# SparkFun-74HC4051-8-Channel-Mux-Breakout.net
KiCad netlist of a schematic drawn in EAGLE
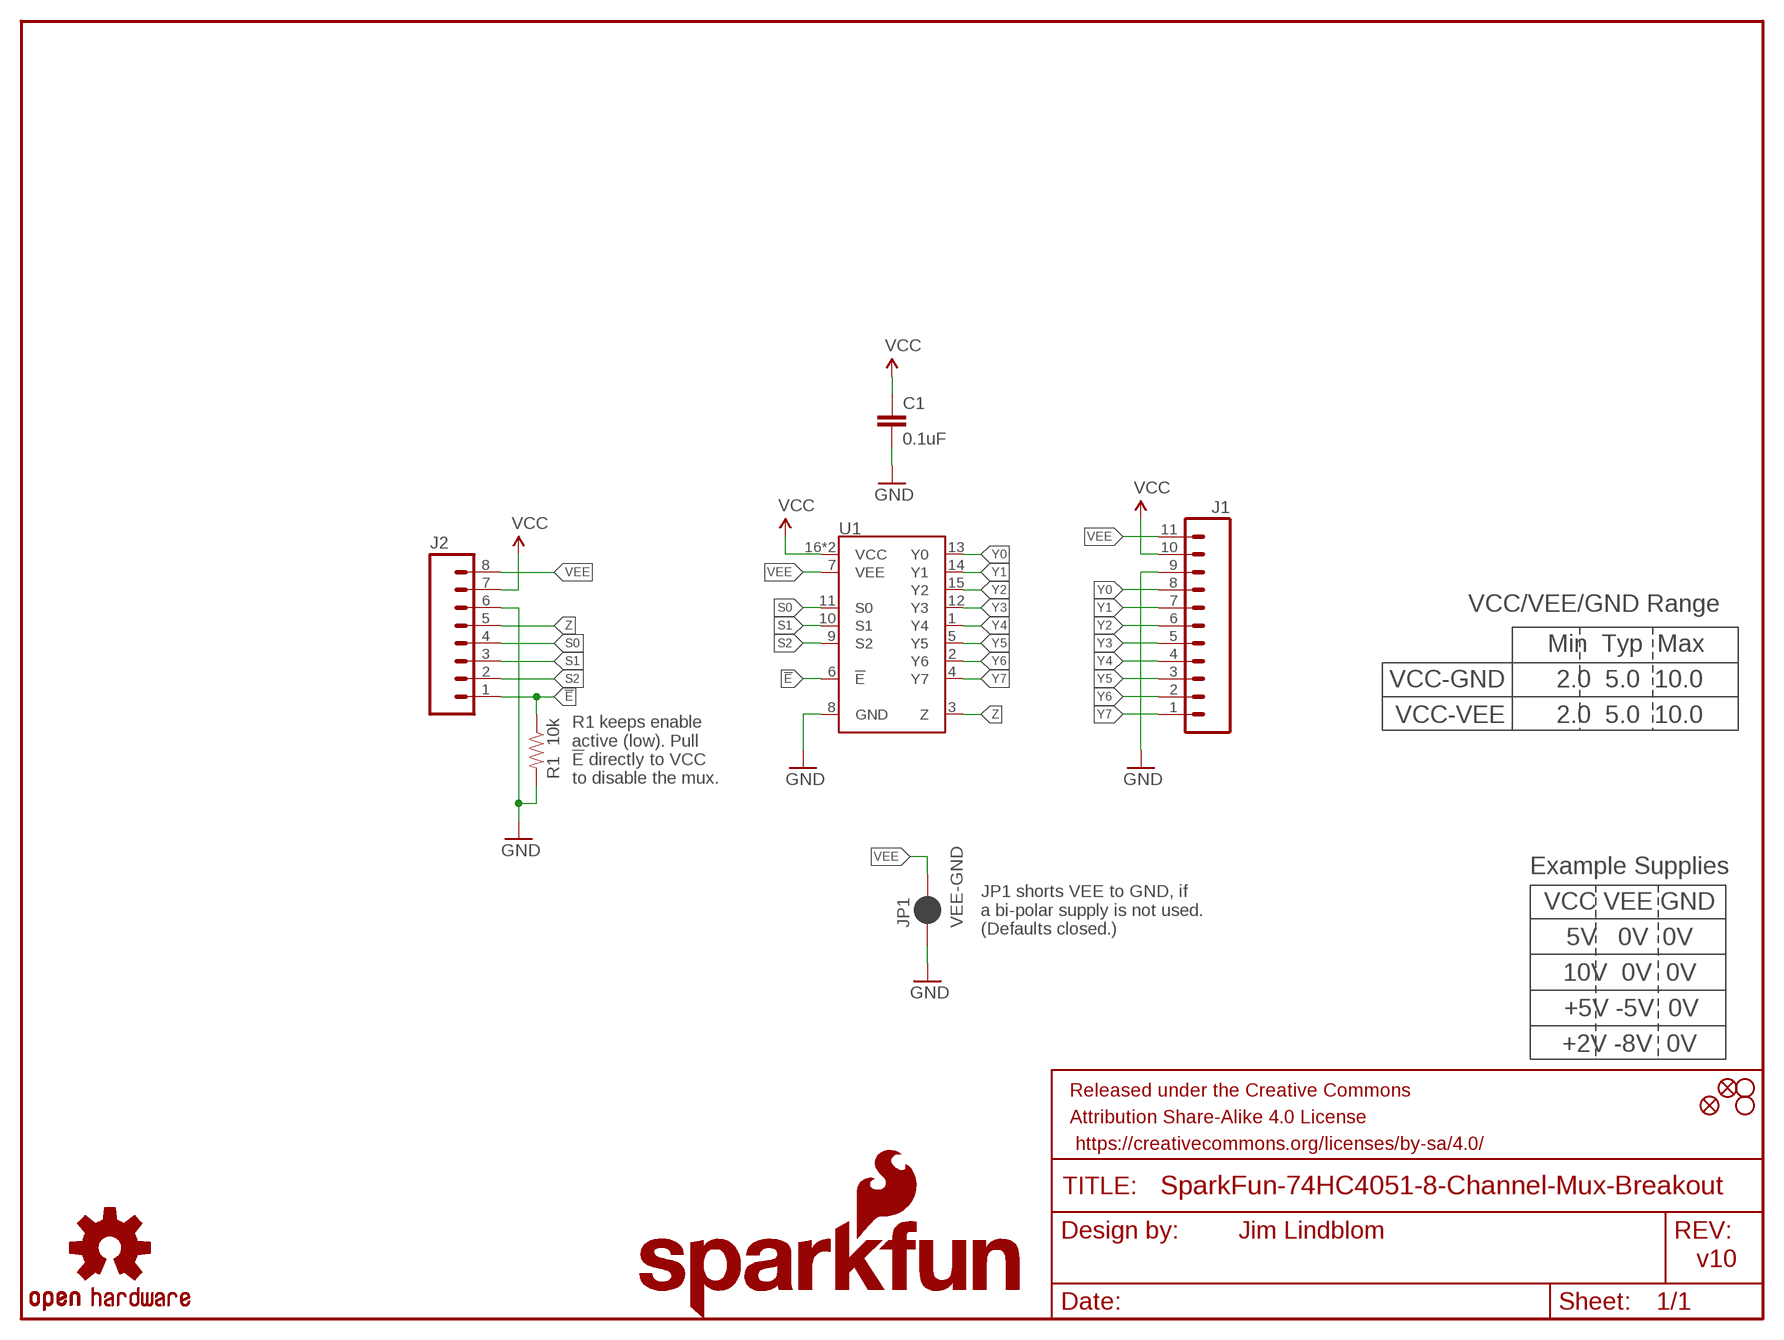
[diagram p0: schematic, sheet 1]

(export (version "E")
  (design (tool "Eeschema 10.0.6"))
  (components
    (comp (ref "C1")
      (value "0.1uF")
      (footprint "eagle-import:0603")
      (libsource (lib "eagle-import") (part "0.1UF-0603-25V-(+80/-20%)"))
    )
    (comp (ref "FD1")
      (value "FIDUCIAL1X2")
      (footprint "eagle-import:FIDUCIAL-1X2")
      (libsource (lib "eagle-import") (part "FIDUCIAL1X2"))
    )
    (comp (ref "FD2")
      (value "FIDUCIAL1X2")
      (footprint "eagle-import:FIDUCIAL-1X2")
      (libsource (lib "eagle-import") (part "FIDUCIAL1X2"))
    )
    (comp (ref "FRAME1")
      (value "FRAME-LETTER")
      (footprint "eagle-import:CREATIVE_COMMONS")
      (libsource (lib "eagle-import") (part "FRAME-LETTER"))
    )
    (comp (ref "H1")
      (value "STAND-OFF")
      (footprint "eagle-import:STAND-OFF")
      (libsource (lib "eagle-import") (part "STAND-OFF"))
    )
    (comp (ref "H2")
      (value "STAND-OFF")
      (footprint "eagle-import:STAND-OFF")
      (libsource (lib "eagle-import") (part "STAND-OFF"))
    )
    (comp (ref "J1")
      (value "M11PTH")
      (footprint "eagle-import:1X11")
      (libsource (lib "eagle-import") (part "M11PTH"))
    )
    (comp (ref "J2")
      (value "M08")
      (footprint "eagle-import:1X08_ROUND")
      (libsource (lib "eagle-import") (part "M08"))
    )
    (comp (ref "JP1")
      (value "VEE-GND")
      (footprint "eagle-import:PAD-JUMPER-2-NC_BY_PASTE_NO_SILK")
      (libsource (lib "eagle-import") (part "JUMPER-PAD-2-NC_BY_PASTENO-SILK"))
    )
    (comp (ref "LOGO1")
      (value "SFE_LOGO_FLAME.1_INCH")
      (footprint "eagle-import:SFE_LOGO_FLAME_.1")
      (libsource (lib "eagle-import") (part "SFE_LOGO_FLAME.1_INCH"))
    )
    (comp (ref "LOGO2")
      (value "OSHW-LOGOMINI")
      (footprint "eagle-import:OSHW-LOGO-MINI")
      (libsource (lib "eagle-import") (part "OSHW-LOGOMINI"))
    )
    (comp (ref "LOGO3")
      (value "SFE_LOGO_NAME.1_INCH")
      (footprint "eagle-import:SFE_LOGO_NAME_.1")
      (libsource (lib "eagle-import") (part "SFE_LOGO_NAME.1_INCH"))
    )
    (comp (ref "R1")
      (value "10k")
      (footprint "eagle-import:0603")
      (libsource (lib "eagle-import") (part "10KOHM-0603-1/10W-1%"))
    )
    (comp (ref "U1")
      (value "74HC4051BQ")
      (footprint "eagle-import:DHVQFN-16-2.5X3.5MM")
      (libsource (lib "eagle-import") (part "744051BQHC"))
    )
  )
  (nets
    (net (code "1") (name "/~{E}") (class "Default")
      (node (ref "J2") (pin "1") (pinfunction "1_1") (pintype "passive"))
      (node (ref "R1") (pin "1") (pinfunction "1_1") (pintype "passive"))
      (node (ref "U1") (pin "6") (pinfunction "~{E}_6") (pintype "bidirectional"))
    )
    (net (code "2") (name "GND") (class "Default")
      (node (ref "C1") (pin "2") (pinfunction "2_2") (pintype "passive"))
      (node (ref "J1") (pin "9") (pinfunction "9_9") (pintype "passive"))
      (node (ref "J2") (pin "6") (pinfunction "6_6") (pintype "passive"))
      (node (ref "JP1") (pin "1") (pinfunction "1_1") (pintype "passive"))
      (node (ref "R1") (pin "2") (pinfunction "2_2") (pintype "passive"))
      (node (ref "U1") (pin "8") (pinfunction "GND_8") (pintype "bidirectional"))
    )
    (net (code "3") (name "S0") (class "Default")
      (node (ref "J2") (pin "4") (pinfunction "4_4") (pintype "passive"))
      (node (ref "U1") (pin "11") (pinfunction "S0_11") (pintype "bidirectional"))
    )
    (net (code "4") (name "S1") (class "Default")
      (node (ref "J2") (pin "3") (pinfunction "3_3") (pintype "passive"))
      (node (ref "U1") (pin "10") (pinfunction "S1_10") (pintype "bidirectional"))
    )
    (net (code "5") (name "S2") (class "Default")
      (node (ref "J2") (pin "2") (pinfunction "2_2") (pintype "passive"))
      (node (ref "U1") (pin "9") (pinfunction "S2_9") (pintype "bidirectional"))
    )
    (net (code "6") (name "VCC") (class "Default")
      (node (ref "C1") (pin "1") (pinfunction "1_1") (pintype "passive"))
      (node (ref "J1") (pin "10") (pinfunction "10_10") (pintype "passive"))
      (node (ref "J2") (pin "7") (pinfunction "7_7") (pintype "passive"))
      (node (ref "U1") (pin "16") (pinfunction "VCC_16") (pintype "bidirectional"))
      (node (ref "U1") (pin "EP") (pinfunction "VCC_EP") (pintype "bidirectional"))
    )
    (net (code "7") (name "VEE") (class "Default")
      (node (ref "J1") (pin "11") (pinfunction "11_11") (pintype "passive"))
      (node (ref "J2") (pin "8") (pinfunction "8_8") (pintype "passive"))
      (node (ref "JP1") (pin "2") (pinfunction "2_2") (pintype "passive"))
      (node (ref "U1") (pin "7") (pinfunction "VEE_7") (pintype "bidirectional"))
    )
    (net (code "8") (name "Y0") (class "Default")
      (node (ref "J1") (pin "8") (pinfunction "8_8") (pintype "passive"))
      (node (ref "U1") (pin "13") (pinfunction "Y0_13") (pintype "bidirectional"))
    )
    (net (code "9") (name "Y1") (class "Default")
      (node (ref "J1") (pin "7") (pinfunction "7_7") (pintype "passive"))
      (node (ref "U1") (pin "14") (pinfunction "Y1_14") (pintype "bidirectional"))
    )
    (net (code "10") (name "Y2") (class "Default")
      (node (ref "J1") (pin "6") (pinfunction "6_6") (pintype "passive"))
      (node (ref "U1") (pin "15") (pinfunction "Y2_15") (pintype "bidirectional"))
    )
    (net (code "11") (name "Y3") (class "Default")
      (node (ref "J1") (pin "5") (pinfunction "5_5") (pintype "passive"))
      (node (ref "U1") (pin "12") (pinfunction "Y3_12") (pintype "bidirectional"))
    )
    (net (code "12") (name "Y4") (class "Default")
      (node (ref "J1") (pin "4") (pinfunction "4_4") (pintype "passive"))
      (node (ref "U1") (pin "1") (pinfunction "Y4_1") (pintype "bidirectional"))
    )
    (net (code "13") (name "Y5") (class "Default")
      (node (ref "J1") (pin "3") (pinfunction "3_3") (pintype "passive"))
      (node (ref "U1") (pin "5") (pinfunction "Y5_5") (pintype "bidirectional"))
    )
    (net (code "14") (name "Y6") (class "Default")
      (node (ref "J1") (pin "2") (pinfunction "2_2") (pintype "passive"))
      (node (ref "U1") (pin "2") (pinfunction "Y6_2") (pintype "bidirectional"))
    )
    (net (code "15") (name "Y7") (class "Default")
      (node (ref "J1") (pin "1") (pinfunction "1_1") (pintype "passive"))
      (node (ref "U1") (pin "4") (pinfunction "Y7_4") (pintype "bidirectional"))
    )
    (net (code "16") (name "Z") (class "Default")
      (node (ref "J2") (pin "5") (pinfunction "5_5") (pintype "passive"))
      (node (ref "U1") (pin "3") (pinfunction "Z_3") (pintype "bidirectional"))
    )
  )
)
